# Regulator_3v3-250mA_MCP1702.net
KiCad netlist of a schematic drawn in Altium Designer
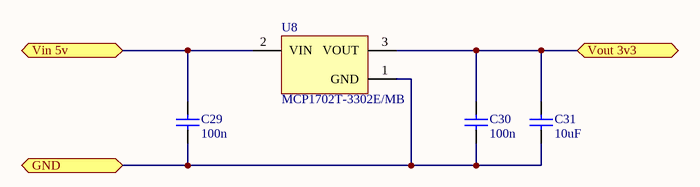
[diagram p0: Regulator 3v3-250mA MCP1702.SchDoc]

(export (version "E")
  (design (tool "Eeschema 10.0.6"))
  (components
    (comp (ref "C29")
      (value "100n")
      (footprint "C0805")
      (fields (field (name "TOLERANCE") "0.1") (field (name "AUTHOR") "Willy Pietersz"))
      (libsource (lib "OurDb") (part "cap_NonPolar"))
    )
    (comp (ref "C30")
      (value "100n")
      (footprint "C0805")
      (fields (field (name "TOLERANCE") "0.1") (field (name "AUTHOR") "Willy Pietersz"))
      (libsource (lib "OurDb") (part "cap_NonPolar"))
    )
    (comp (ref "C31")
      (value "10uF")
      (footprint "C1206")
      (fields
        (field (name "VOLTAGE") "10V")
        (field (name "TOLERANCE") "0.1")
        (field (name "AUTHOR") "Willem Pietersz")
      )
      (libsource (lib "OurDb") (part "cap_NonPolar"))
    )
    (comp (ref "U8")
      (value "MCP1702T-3302E/MB")
      (footprint "SOT-89-MB3_N")
      (fields (field (name "PUBLISHER") "Altium Limited"))
      (libsource (lib "AltiumDatabaseSelection") (part "MCP1702T-3302E/MB"))
    )
  )
  (nets
    (net (code "1") (name "/GND") (class "Default")
      (node (ref "C29") (pin "1") (pinfunction "1_1") (pintype "passive"))
      (node (ref "C30") (pin "1") (pinfunction "1_1") (pintype "passive"))
      (node (ref "C31") (pin "1") (pinfunction "1_1") (pintype "passive"))
      (node (ref "U8") (pin "1") (pinfunction "GND_1") (pintype "power_in"))
    )
    (net (code "2") (name "/Vin 5v") (class "Default")
      (node (ref "C29") (pin "2") (pinfunction "2_2") (pintype "passive"))
      (node (ref "U8") (pin "2") (pinfunction "VIN_2") (pintype "power_in"))
    )
    (net (code "3") (name "/Vout 3v3") (class "Default")
      (node (ref "C30") (pin "2") (pinfunction "2_2") (pintype "passive"))
      (node (ref "C31") (pin "2") (pinfunction "2_2") (pintype "passive"))
      (node (ref "U8") (pin "3") (pinfunction "VOUT_3") (pintype "power_in"))
    )
  )
)
